# ADC_OLD.net
KiCad netlist of a schematic drawn in Altium Designer
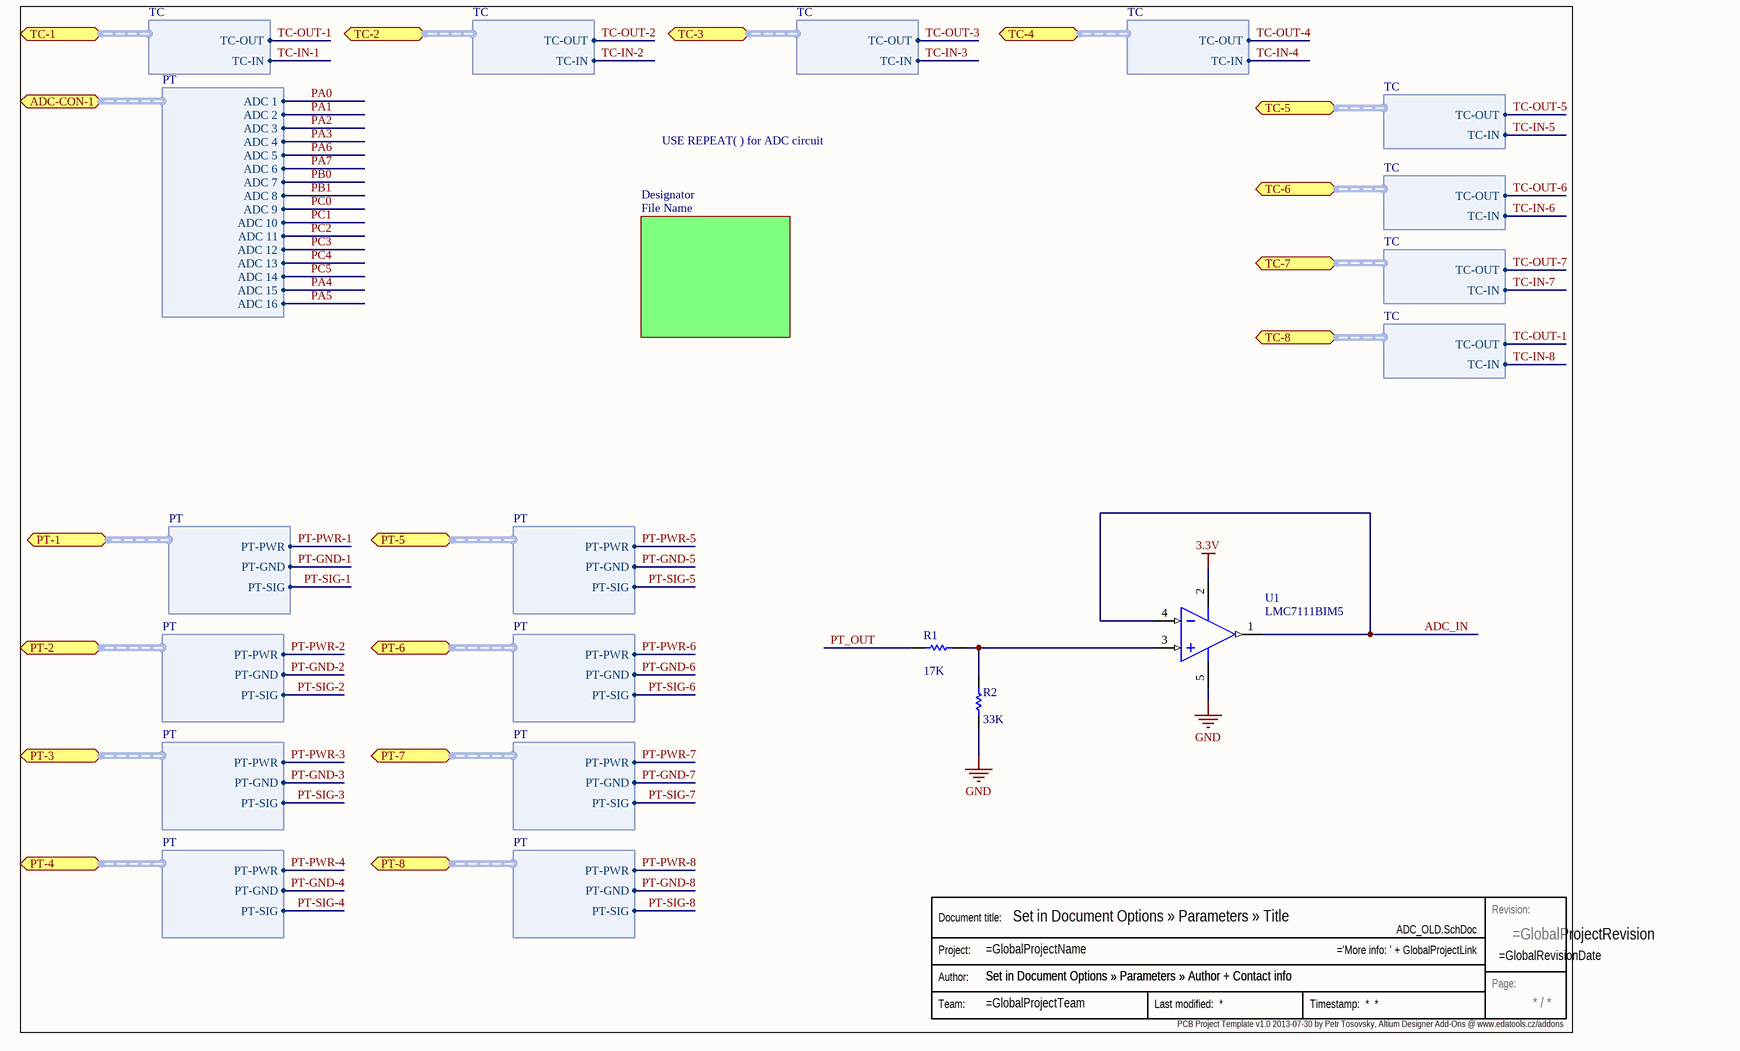
[diagram p0: ADC_OLD.SchDoc]

(export (version "E")
  (design (tool "Eeschema 10.0.6"))
  (components
    (comp (ref "R1")
      (value "17K")
      (footprint "AXIAL-0.3")
      (description "Resistor")
      (fields (field (name "PUBLISHER") "Altium Limited"))
      (libsource (lib "Miscellaneous Devices") (part "Res1"))
    )
    (comp (ref "R2")
      (value "~")
      (footprint "AXIAL-0.3")
      (description "Resistor")
      (fields (field (name "RES-33K") "33K") (field (name "PUBLISHER") "Altium Limited"))
      (libsource (lib "Miscellaneous Devices") (part "Res1"))
    )
    (comp (ref "Stamp") (value "Stamp") (libsource (lib "ShieldsLib") (part "Stamp")))
    (comp (ref "U1")
      (value "LMC7111BIM5")
      (footprint "MF05A_N")
      (description "Tiny CMOS Operational Amplifier with Rail-to-Rail Input and Output, 5-pin SOT-23")
      (fields (field (name "MANUFACTURER") "National Semiconductor"))
      (libsource (lib "National Semiconductor Amplifier") (part "LMC7111BIM5"))
    )
  )
  (nets
    (net (code "3") (name "/ADC_IN") (class "Default")
      (node (ref "U1") (pin "1") (pinfunction "OUT_1") (pintype "output"))
      (node (ref "U1") (pin "4") (pinfunction "IN-_4") (pintype "input"))
    )
    (net (code "44") (name "/PT_OUT") (class "Default")
      (node (ref "R1") (pin "1") (pinfunction "1_1") (pintype "passive"))
    )
    (net (code "62") (name "3.3V") (class "Default")
      (node (ref "U1") (pin "2") (pinfunction "V+_2") (pintype "power_in"))
    )
    (net (code "63") (name "GND") (class "Default")
      (node (ref "R2") (pin "1") (pinfunction "1_1") (pintype "passive"))
      (node (ref "U1") (pin "5") (pinfunction "V-_5") (pintype "power_in"))
    )
    (net (code "64") (name "Net-(U1-IN+)") (class "Default")
      (node (ref "R1") (pin "2") (pinfunction "2_2") (pintype "passive"))
      (node (ref "R2") (pin "2") (pinfunction "2_2") (pintype "passive"))
      (node (ref "U1") (pin "3") (pinfunction "IN+_3") (pintype "input"))
    )
  )
)
